# mother_v0.net
KiCad netlist of a schematic drawn in EAGLE
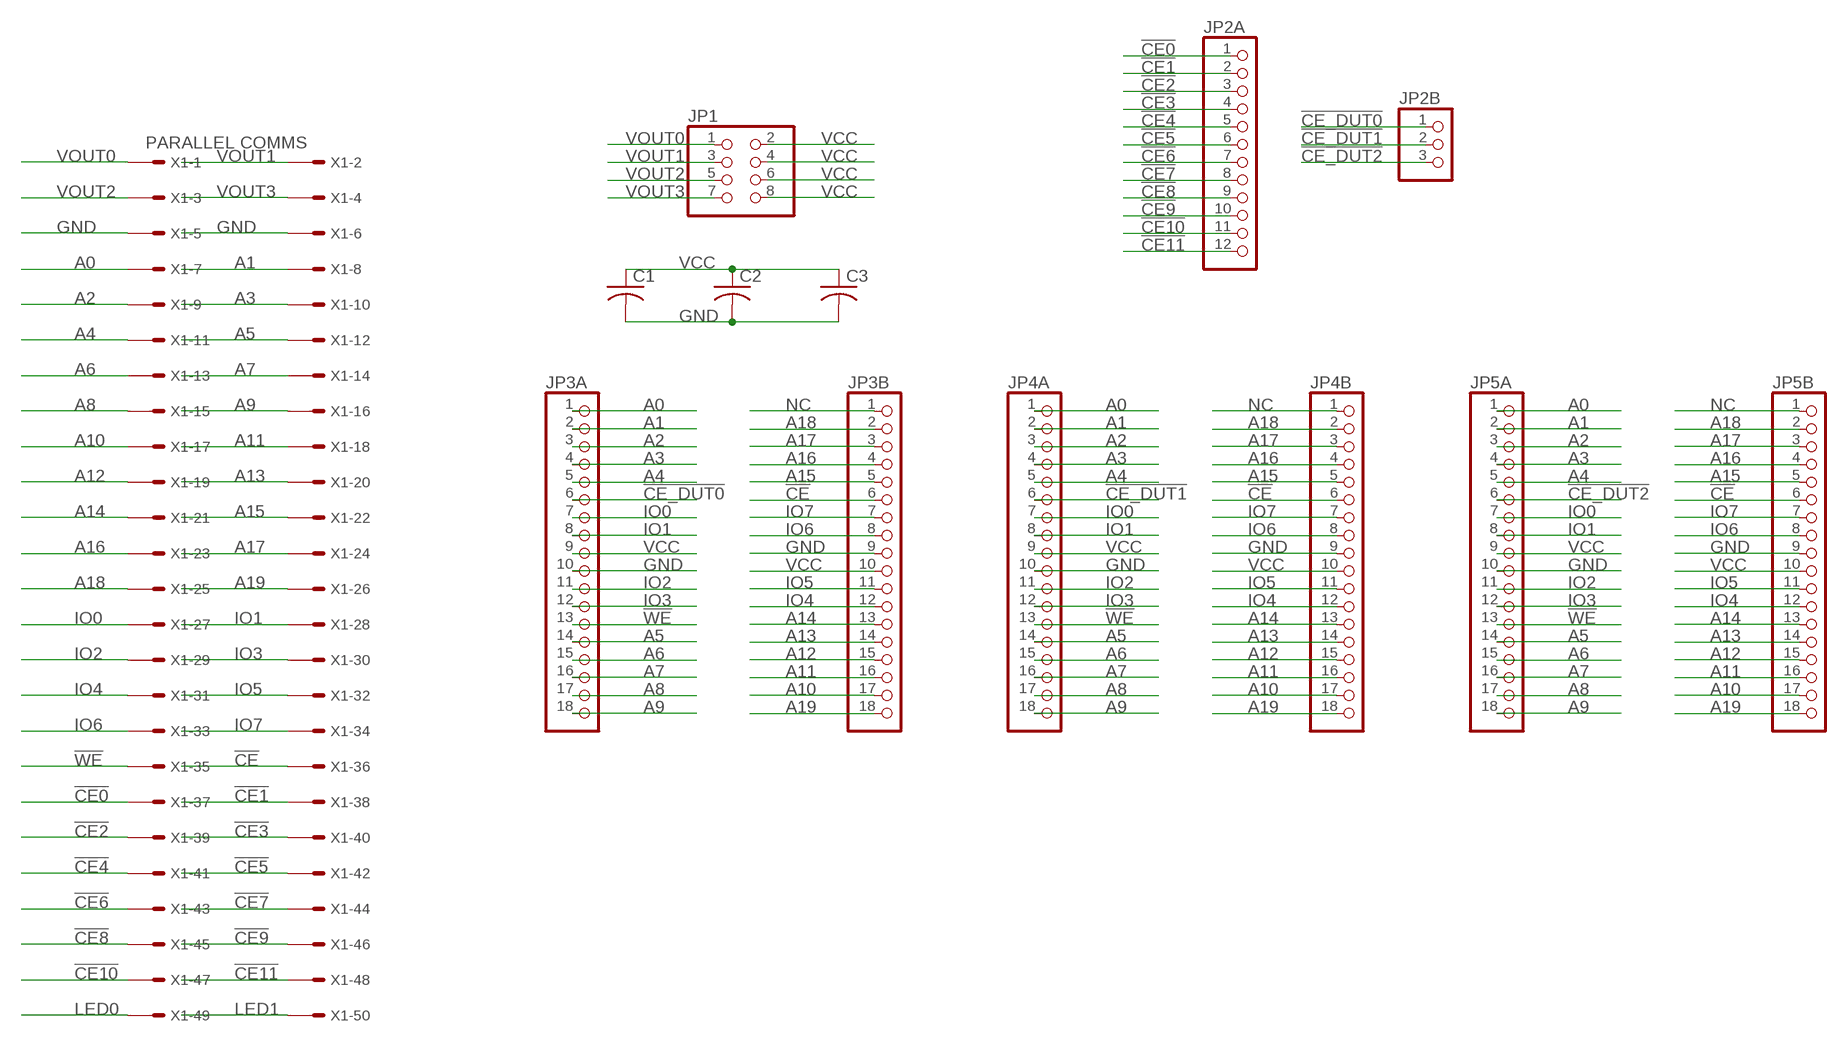
[diagram p0: schematic, sheet 1]

(export (version "E")
  (design (tool "Eeschema 10.0.6"))
  (components
    (comp (ref "C1")
      (value "C-USC0805")
      (footprint "eagle-import:C0805")
      (libsource (lib "eagle-import") (part "C-USC0805"))
    )
    (comp (ref "C2")
      (value "C-USC0805")
      (footprint "eagle-import:C0805")
      (libsource (lib "eagle-import") (part "C-USC0805"))
    )
    (comp (ref "C3")
      (value "C-USC0805")
      (footprint "eagle-import:C0805")
      (libsource (lib "eagle-import") (part "C-USC0805"))
    )
    (comp (ref "JP1")
      (value "PINHD-2X4")
      (footprint "eagle-import:2X04")
      (libsource (lib "eagle-import") (part "PINHD-2X4"))
    )
    (comp (ref "JP2A")
      (value "PINHD-1X12")
      (footprint "eagle-import:1X12")
      (libsource (lib "eagle-import") (part "PINHD-1X12"))
    )
    (comp (ref "JP2B")
      (value "PINHD-1X3")
      (footprint "eagle-import:1X03")
      (libsource (lib "eagle-import") (part "PINHD-1X3"))
    )
    (comp (ref "JP3A")
      (value "PINHD-1X18")
      (footprint "eagle-import:1X18")
      (libsource (lib "eagle-import") (part "PINHD-1X18"))
    )
    (comp (ref "JP3B")
      (value "PINHD-1X18")
      (footprint "eagle-import:1X18")
      (libsource (lib "eagle-import") (part "PINHD-1X18"))
    )
    (comp (ref "JP4A")
      (value "PINHD-1X18")
      (footprint "eagle-import:1X18")
      (libsource (lib "eagle-import") (part "PINHD-1X18"))
    )
    (comp (ref "JP4B")
      (value "PINHD-1X18")
      (footprint "eagle-import:1X18")
      (libsource (lib "eagle-import") (part "PINHD-1X18"))
    )
    (comp (ref "JP5A")
      (value "PINHD-1X18")
      (footprint "eagle-import:1X18")
      (libsource (lib "eagle-import") (part "PINHD-1X18"))
    )
    (comp (ref "JP5B")
      (value "PINHD-1X18")
      (footprint "eagle-import:1X18")
      (libsource (lib "eagle-import") (part "PINHD-1X18"))
    )
    (comp (ref "X1")
      (value "PARALLEL COMMS")
      (footprint "eagle-import:057-050-1")
      (libsource (lib "eagle-import") (part "057-050-1"))
    )
  )
  (nets
    (net (code "1") (name "/A0") (class "Default")
      (node (ref "JP3A") (pin "1") (pinfunction "1_1") (pintype "passive"))
      (node (ref "JP4A") (pin "1") (pinfunction "1_1") (pintype "passive"))
      (node (ref "JP5A") (pin "1") (pinfunction "1_1") (pintype "passive"))
      (node (ref "X1") (pin "7") (pinfunction "S_7") (pintype "passive"))
    )
    (net (code "2") (name "/A1") (class "Default")
      (node (ref "JP3A") (pin "2") (pinfunction "2_2") (pintype "passive"))
      (node (ref "JP4A") (pin "2") (pinfunction "2_2") (pintype "passive"))
      (node (ref "JP5A") (pin "2") (pinfunction "2_2") (pintype "passive"))
      (node (ref "X1") (pin "8") (pinfunction "S_8") (pintype "passive"))
    )
    (net (code "3") (name "/A2") (class "Default")
      (node (ref "JP3A") (pin "3") (pinfunction "3_3") (pintype "passive"))
      (node (ref "JP4A") (pin "3") (pinfunction "3_3") (pintype "passive"))
      (node (ref "JP5A") (pin "3") (pinfunction "3_3") (pintype "passive"))
      (node (ref "X1") (pin "9") (pinfunction "S_9") (pintype "passive"))
    )
    (net (code "4") (name "/A3") (class "Default")
      (node (ref "JP3A") (pin "4") (pinfunction "4_4") (pintype "passive"))
      (node (ref "JP4A") (pin "4") (pinfunction "4_4") (pintype "passive"))
      (node (ref "JP5A") (pin "4") (pinfunction "4_4") (pintype "passive"))
      (node (ref "X1") (pin "10") (pinfunction "S_10") (pintype "passive"))
    )
    (net (code "5") (name "/A4") (class "Default")
      (node (ref "JP3A") (pin "5") (pinfunction "5_5") (pintype "passive"))
      (node (ref "JP4A") (pin "5") (pinfunction "5_5") (pintype "passive"))
      (node (ref "JP5A") (pin "5") (pinfunction "5_5") (pintype "passive"))
      (node (ref "X1") (pin "11") (pinfunction "S_11") (pintype "passive"))
    )
    (net (code "6") (name "/A5") (class "Default")
      (node (ref "JP3A") (pin "14") (pinfunction "14_14") (pintype "passive"))
      (node (ref "JP4A") (pin "14") (pinfunction "14_14") (pintype "passive"))
      (node (ref "JP5A") (pin "14") (pinfunction "14_14") (pintype "passive"))
      (node (ref "X1") (pin "12") (pinfunction "S_12") (pintype "passive"))
    )
    (net (code "7") (name "/A6") (class "Default")
      (node (ref "JP3A") (pin "15") (pinfunction "15_15") (pintype "passive"))
      (node (ref "JP4A") (pin "15") (pinfunction "15_15") (pintype "passive"))
      (node (ref "JP5A") (pin "15") (pinfunction "15_15") (pintype "passive"))
      (node (ref "X1") (pin "13") (pinfunction "S_13") (pintype "passive"))
    )
    (net (code "8") (name "/A7") (class "Default")
      (node (ref "JP3A") (pin "16") (pinfunction "16_16") (pintype "passive"))
      (node (ref "JP4A") (pin "16") (pinfunction "16_16") (pintype "passive"))
      (node (ref "JP5A") (pin "16") (pinfunction "16_16") (pintype "passive"))
      (node (ref "X1") (pin "14") (pinfunction "S_14") (pintype "passive"))
    )
    (net (code "9") (name "/A8") (class "Default")
      (node (ref "JP3A") (pin "17") (pinfunction "17_17") (pintype "passive"))
      (node (ref "JP4A") (pin "17") (pinfunction "17_17") (pintype "passive"))
      (node (ref "JP5A") (pin "17") (pinfunction "17_17") (pintype "passive"))
      (node (ref "X1") (pin "15") (pinfunction "S_15") (pintype "passive"))
    )
    (net (code "10") (name "/A9") (class "Default")
      (node (ref "JP3A") (pin "18") (pinfunction "18_18") (pintype "passive"))
      (node (ref "JP4A") (pin "18") (pinfunction "18_18") (pintype "passive"))
      (node (ref "JP5A") (pin "18") (pinfunction "18_18") (pintype "passive"))
      (node (ref "X1") (pin "16") (pinfunction "S_16") (pintype "passive"))
    )
    (net (code "11") (name "/A10") (class "Default")
      (node (ref "JP3B") (pin "17") (pinfunction "17_17") (pintype "passive"))
      (node (ref "JP4B") (pin "17") (pinfunction "17_17") (pintype "passive"))
      (node (ref "JP5B") (pin "17") (pinfunction "17_17") (pintype "passive"))
      (node (ref "X1") (pin "17") (pinfunction "S_17") (pintype "passive"))
    )
    (net (code "12") (name "/A11") (class "Default")
      (node (ref "JP3B") (pin "16") (pinfunction "16_16") (pintype "passive"))
      (node (ref "JP4B") (pin "16") (pinfunction "16_16") (pintype "passive"))
      (node (ref "JP5B") (pin "16") (pinfunction "16_16") (pintype "passive"))
      (node (ref "X1") (pin "18") (pinfunction "S_18") (pintype "passive"))
    )
    (net (code "13") (name "/A12") (class "Default")
      (node (ref "JP3B") (pin "15") (pinfunction "15_15") (pintype "passive"))
      (node (ref "JP4B") (pin "15") (pinfunction "15_15") (pintype "passive"))
      (node (ref "JP5B") (pin "15") (pinfunction "15_15") (pintype "passive"))
      (node (ref "X1") (pin "19") (pinfunction "S_19") (pintype "passive"))
    )
    (net (code "14") (name "/A13") (class "Default")
      (node (ref "JP3B") (pin "14") (pinfunction "14_14") (pintype "passive"))
      (node (ref "JP4B") (pin "14") (pinfunction "14_14") (pintype "passive"))
      (node (ref "JP5B") (pin "14") (pinfunction "14_14") (pintype "passive"))
      (node (ref "X1") (pin "20") (pinfunction "S_20") (pintype "passive"))
    )
    (net (code "15") (name "/A14") (class "Default")
      (node (ref "JP3B") (pin "13") (pinfunction "13_13") (pintype "passive"))
      (node (ref "JP4B") (pin "13") (pinfunction "13_13") (pintype "passive"))
      (node (ref "JP5B") (pin "13") (pinfunction "13_13") (pintype "passive"))
      (node (ref "X1") (pin "21") (pinfunction "S_21") (pintype "passive"))
    )
    (net (code "16") (name "/A15") (class "Default")
      (node (ref "JP3B") (pin "5") (pinfunction "5_5") (pintype "passive"))
      (node (ref "JP4B") (pin "5") (pinfunction "5_5") (pintype "passive"))
      (node (ref "JP5B") (pin "5") (pinfunction "5_5") (pintype "passive"))
      (node (ref "X1") (pin "22") (pinfunction "S_22") (pintype "passive"))
    )
    (net (code "17") (name "/A16") (class "Default")
      (node (ref "JP3B") (pin "4") (pinfunction "4_4") (pintype "passive"))
      (node (ref "JP4B") (pin "4") (pinfunction "4_4") (pintype "passive"))
      (node (ref "JP5B") (pin "4") (pinfunction "4_4") (pintype "passive"))
      (node (ref "X1") (pin "23") (pinfunction "S_23") (pintype "passive"))
    )
    (net (code "18") (name "/A17") (class "Default")
      (node (ref "JP3B") (pin "3") (pinfunction "3_3") (pintype "passive"))
      (node (ref "JP4B") (pin "3") (pinfunction "3_3") (pintype "passive"))
      (node (ref "JP5B") (pin "3") (pinfunction "3_3") (pintype "passive"))
      (node (ref "X1") (pin "24") (pinfunction "S_24") (pintype "passive"))
    )
    (net (code "19") (name "/A18") (class "Default")
      (node (ref "JP3B") (pin "2") (pinfunction "2_2") (pintype "passive"))
      (node (ref "JP4B") (pin "2") (pinfunction "2_2") (pintype "passive"))
      (node (ref "JP5B") (pin "2") (pinfunction "2_2") (pintype "passive"))
      (node (ref "X1") (pin "25") (pinfunction "S_25") (pintype "passive"))
    )
    (net (code "20") (name "/A19") (class "Default")
      (node (ref "JP3B") (pin "18") (pinfunction "18_18") (pintype "passive"))
      (node (ref "JP4B") (pin "18") (pinfunction "18_18") (pintype "passive"))
      (node (ref "JP5B") (pin "18") (pinfunction "18_18") (pintype "passive"))
      (node (ref "X1") (pin "26") (pinfunction "S_26") (pintype "passive"))
    )
    (net (code "21") (name "/GND") (class "Default")
      (node (ref "C1") (pin "2") (pinfunction "2_2") (pintype "passive"))
      (node (ref "C2") (pin "2") (pinfunction "2_2") (pintype "passive"))
      (node (ref "C3") (pin "2") (pinfunction "2_2") (pintype "passive"))
      (node (ref "JP3A") (pin "10") (pinfunction "10_10") (pintype "passive"))
      (node (ref "JP3B") (pin "9") (pinfunction "9_9") (pintype "passive"))
      (node (ref "JP4A") (pin "10") (pinfunction "10_10") (pintype "passive"))
      (node (ref "JP4B") (pin "9") (pinfunction "9_9") (pintype "passive"))
      (node (ref "JP5A") (pin "10") (pinfunction "10_10") (pintype "passive"))
      (node (ref "JP5B") (pin "9") (pinfunction "9_9") (pintype "passive"))
      (node (ref "X1") (pin "5") (pinfunction "S_5") (pintype "passive"))
      (node (ref "X1") (pin "6") (pinfunction "S_6") (pintype "passive"))
    )
    (net (code "22") (name "/IO0") (class "Default")
      (node (ref "JP3A") (pin "7") (pinfunction "7_7") (pintype "passive"))
      (node (ref "JP4A") (pin "7") (pinfunction "7_7") (pintype "passive"))
      (node (ref "JP5A") (pin "7") (pinfunction "7_7") (pintype "passive"))
      (node (ref "X1") (pin "27") (pinfunction "S_27") (pintype "passive"))
    )
    (net (code "23") (name "/IO1") (class "Default")
      (node (ref "JP3A") (pin "8") (pinfunction "8_8") (pintype "passive"))
      (node (ref "JP4A") (pin "8") (pinfunction "8_8") (pintype "passive"))
      (node (ref "JP5A") (pin "8") (pinfunction "8_8") (pintype "passive"))
      (node (ref "X1") (pin "28") (pinfunction "S_28") (pintype "passive"))
    )
    (net (code "24") (name "/IO2") (class "Default")
      (node (ref "JP3A") (pin "11") (pinfunction "11_11") (pintype "passive"))
      (node (ref "JP4A") (pin "11") (pinfunction "11_11") (pintype "passive"))
      (node (ref "JP5A") (pin "11") (pinfunction "11_11") (pintype "passive"))
      (node (ref "X1") (pin "29") (pinfunction "S_29") (pintype "passive"))
    )
    (net (code "25") (name "/IO3") (class "Default")
      (node (ref "JP3A") (pin "12") (pinfunction "12_12") (pintype "passive"))
      (node (ref "JP4A") (pin "12") (pinfunction "12_12") (pintype "passive"))
      (node (ref "JP5A") (pin "12") (pinfunction "12_12") (pintype "passive"))
      (node (ref "X1") (pin "30") (pinfunction "S_30") (pintype "passive"))
    )
    (net (code "26") (name "/IO4") (class "Default")
      (node (ref "JP3B") (pin "12") (pinfunction "12_12") (pintype "passive"))
      (node (ref "JP4B") (pin "12") (pinfunction "12_12") (pintype "passive"))
      (node (ref "JP5B") (pin "12") (pinfunction "12_12") (pintype "passive"))
      (node (ref "X1") (pin "31") (pinfunction "S_31") (pintype "passive"))
    )
    (net (code "27") (name "/IO5") (class "Default")
      (node (ref "JP3B") (pin "11") (pinfunction "11_11") (pintype "passive"))
      (node (ref "JP4B") (pin "11") (pinfunction "11_11") (pintype "passive"))
      (node (ref "JP5B") (pin "11") (pinfunction "11_11") (pintype "passive"))
      (node (ref "X1") (pin "32") (pinfunction "S_32") (pintype "passive"))
    )
    (net (code "28") (name "/IO6") (class "Default")
      (node (ref "JP3B") (pin "8") (pinfunction "8_8") (pintype "passive"))
      (node (ref "JP4B") (pin "8") (pinfunction "8_8") (pintype "passive"))
      (node (ref "JP5B") (pin "8") (pinfunction "8_8") (pintype "passive"))
      (node (ref "X1") (pin "33") (pinfunction "S_33") (pintype "passive"))
    )
    (net (code "29") (name "/IO7") (class "Default")
      (node (ref "JP3B") (pin "7") (pinfunction "7_7") (pintype "passive"))
      (node (ref "JP4B") (pin "7") (pinfunction "7_7") (pintype "passive"))
      (node (ref "JP5B") (pin "7") (pinfunction "7_7") (pintype "passive"))
      (node (ref "X1") (pin "34") (pinfunction "S_34") (pintype "passive"))
    )
    (net (code "30") (name "/LED0") (class "Default")
      (node (ref "X1") (pin "49") (pinfunction "S_49") (pintype "passive"))
    )
    (net (code "31") (name "/LED1") (class "Default")
      (node (ref "X1") (pin "50") (pinfunction "S_50") (pintype "passive"))
    )
    (net (code "32") (name "/NC") (class "Default")
      (node (ref "JP3B") (pin "1") (pinfunction "1_1") (pintype "passive"))
      (node (ref "JP4B") (pin "1") (pinfunction "1_1") (pintype "passive"))
      (node (ref "JP5B") (pin "1") (pinfunction "1_1") (pintype "passive"))
    )
    (net (code "33") (name "/VCC") (class "Default")
      (node (ref "C1") (pin "1") (pinfunction "1_1") (pintype "passive"))
      (node (ref "C2") (pin "1") (pinfunction "1_1") (pintype "passive"))
      (node (ref "C3") (pin "1") (pinfunction "1_1") (pintype "passive"))
      (node (ref "JP1") (pin "2") (pinfunction "2_2") (pintype "passive"))
      (node (ref "JP1") (pin "4") (pinfunction "4_4") (pintype "passive"))
      (node (ref "JP1") (pin "6") (pinfunction "6_6") (pintype "passive"))
      (node (ref "JP1") (pin "8") (pinfunction "8_8") (pintype "passive"))
      (node (ref "JP3A") (pin "9") (pinfunction "9_9") (pintype "passive"))
      (node (ref "JP3B") (pin "10") (pinfunction "10_10") (pintype "passive"))
      (node (ref "JP4A") (pin "9") (pinfunction "9_9") (pintype "passive"))
      (node (ref "JP4B") (pin "10") (pinfunction "10_10") (pintype "passive"))
      (node (ref "JP5A") (pin "9") (pinfunction "9_9") (pintype "passive"))
      (node (ref "JP5B") (pin "10") (pinfunction "10_10") (pintype "passive"))
    )
    (net (code "34") (name "/VOUT0") (class "Default")
      (node (ref "JP1") (pin "1") (pinfunction "1_1") (pintype "passive"))
      (node (ref "X1") (pin "1") (pinfunction "S_1") (pintype "passive"))
    )
    (net (code "35") (name "/VOUT1") (class "Default")
      (node (ref "JP1") (pin "3") (pinfunction "3_3") (pintype "passive"))
      (node (ref "X1") (pin "2") (pinfunction "S_2") (pintype "passive"))
    )
    (net (code "36") (name "/VOUT2") (class "Default")
      (node (ref "JP1") (pin "5") (pinfunction "5_5") (pintype "passive"))
      (node (ref "X1") (pin "3") (pinfunction "S_3") (pintype "passive"))
    )
    (net (code "37") (name "/VOUT3") (class "Default")
      (node (ref "JP1") (pin "7") (pinfunction "7_7") (pintype "passive"))
      (node (ref "X1") (pin "4") (pinfunction "S_4") (pintype "passive"))
    )
    (net (code "38") (name "/~{CE0}") (class "Default")
      (node (ref "JP2A") (pin "1") (pinfunction "1_1") (pintype "passive"))
      (node (ref "X1") (pin "37") (pinfunction "S_37") (pintype "passive"))
    )
    (net (code "39") (name "/~{CE1}") (class "Default")
      (node (ref "JP2A") (pin "2") (pinfunction "2_2") (pintype "passive"))
      (node (ref "X1") (pin "38") (pinfunction "S_38") (pintype "passive"))
    )
    (net (code "40") (name "/~{CE2}") (class "Default")
      (node (ref "JP2A") (pin "3") (pinfunction "3_3") (pintype "passive"))
      (node (ref "X1") (pin "39") (pinfunction "S_39") (pintype "passive"))
    )
    (net (code "41") (name "/~{CE3}") (class "Default")
      (node (ref "JP2A") (pin "4") (pinfunction "4_4") (pintype "passive"))
      (node (ref "X1") (pin "40") (pinfunction "S_40") (pintype "passive"))
    )
    (net (code "42") (name "/~{CE4}") (class "Default")
      (node (ref "JP2A") (pin "5") (pinfunction "5_5") (pintype "passive"))
      (node (ref "X1") (pin "41") (pinfunction "S_41") (pintype "passive"))
    )
    (net (code "43") (name "/~{CE5}") (class "Default")
      (node (ref "JP2A") (pin "6") (pinfunction "6_6") (pintype "passive"))
      (node (ref "X1") (pin "42") (pinfunction "S_42") (pintype "passive"))
    )
    (net (code "44") (name "/~{CE6}") (class "Default")
      (node (ref "JP2A") (pin "7") (pinfunction "7_7") (pintype "passive"))
      (node (ref "X1") (pin "43") (pinfunction "S_43") (pintype "passive"))
    )
    (net (code "45") (name "/~{CE7}") (class "Default")
      (node (ref "JP2A") (pin "8") (pinfunction "8_8") (pintype "passive"))
      (node (ref "X1") (pin "44") (pinfunction "S_44") (pintype "passive"))
    )
    (net (code "46") (name "/~{CE8}") (class "Default")
      (node (ref "JP2A") (pin "9") (pinfunction "9_9") (pintype "passive"))
      (node (ref "X1") (pin "45") (pinfunction "S_45") (pintype "passive"))
    )
    (net (code "47") (name "/~{CE9}") (class "Default")
      (node (ref "JP2A") (pin "10") (pinfunction "10_10") (pintype "passive"))
      (node (ref "X1") (pin "46") (pinfunction "S_46") (pintype "passive"))
    )
    (net (code "48") (name "/~{CE10}") (class "Default")
      (node (ref "JP2A") (pin "11") (pinfunction "11_11") (pintype "passive"))
      (node (ref "X1") (pin "47") (pinfunction "S_47") (pintype "passive"))
    )
    (net (code "49") (name "/~{CE11}") (class "Default")
      (node (ref "JP2A") (pin "12") (pinfunction "12_12") (pintype "passive"))
      (node (ref "X1") (pin "48") (pinfunction "S_48") (pintype "passive"))
    )
    (net (code "50") (name "/~{CE_DUT0}") (class "Default")
      (node (ref "JP2B") (pin "1") (pinfunction "1_1") (pintype "passive"))
      (node (ref "JP3A") (pin "6") (pinfunction "6_6") (pintype "passive"))
    )
    (net (code "51") (name "/~{CE_DUT1}") (class "Default")
      (node (ref "JP2B") (pin "2") (pinfunction "2_2") (pintype "passive"))
      (node (ref "JP4A") (pin "6") (pinfunction "6_6") (pintype "passive"))
    )
    (net (code "52") (name "/~{CE_DUT2}") (class "Default")
      (node (ref "JP2B") (pin "3") (pinfunction "3_3") (pintype "passive"))
      (node (ref "JP5A") (pin "6") (pinfunction "6_6") (pintype "passive"))
    )
    (net (code "53") (name "/~{CE}") (class "Default")
      (node (ref "JP3B") (pin "6") (pinfunction "6_6") (pintype "passive"))
      (node (ref "JP4B") (pin "6") (pinfunction "6_6") (pintype "passive"))
      (node (ref "JP5B") (pin "6") (pinfunction "6_6") (pintype "passive"))
      (node (ref "X1") (pin "36") (pinfunction "S_36") (pintype "passive"))
    )
    (net (code "54") (name "/~{WE}") (class "Default")
      (node (ref "JP3A") (pin "13") (pinfunction "13_13") (pintype "passive"))
      (node (ref "JP4A") (pin "13") (pinfunction "13_13") (pintype "passive"))
      (node (ref "JP5A") (pin "13") (pinfunction "13_13") (pintype "passive"))
      (node (ref "X1") (pin "35") (pinfunction "S_35") (pintype "passive"))
    )
  )
)
